# EVSEInterface_ChargerRelay.net
KiCad netlist of a schematic drawn in Altium Designer
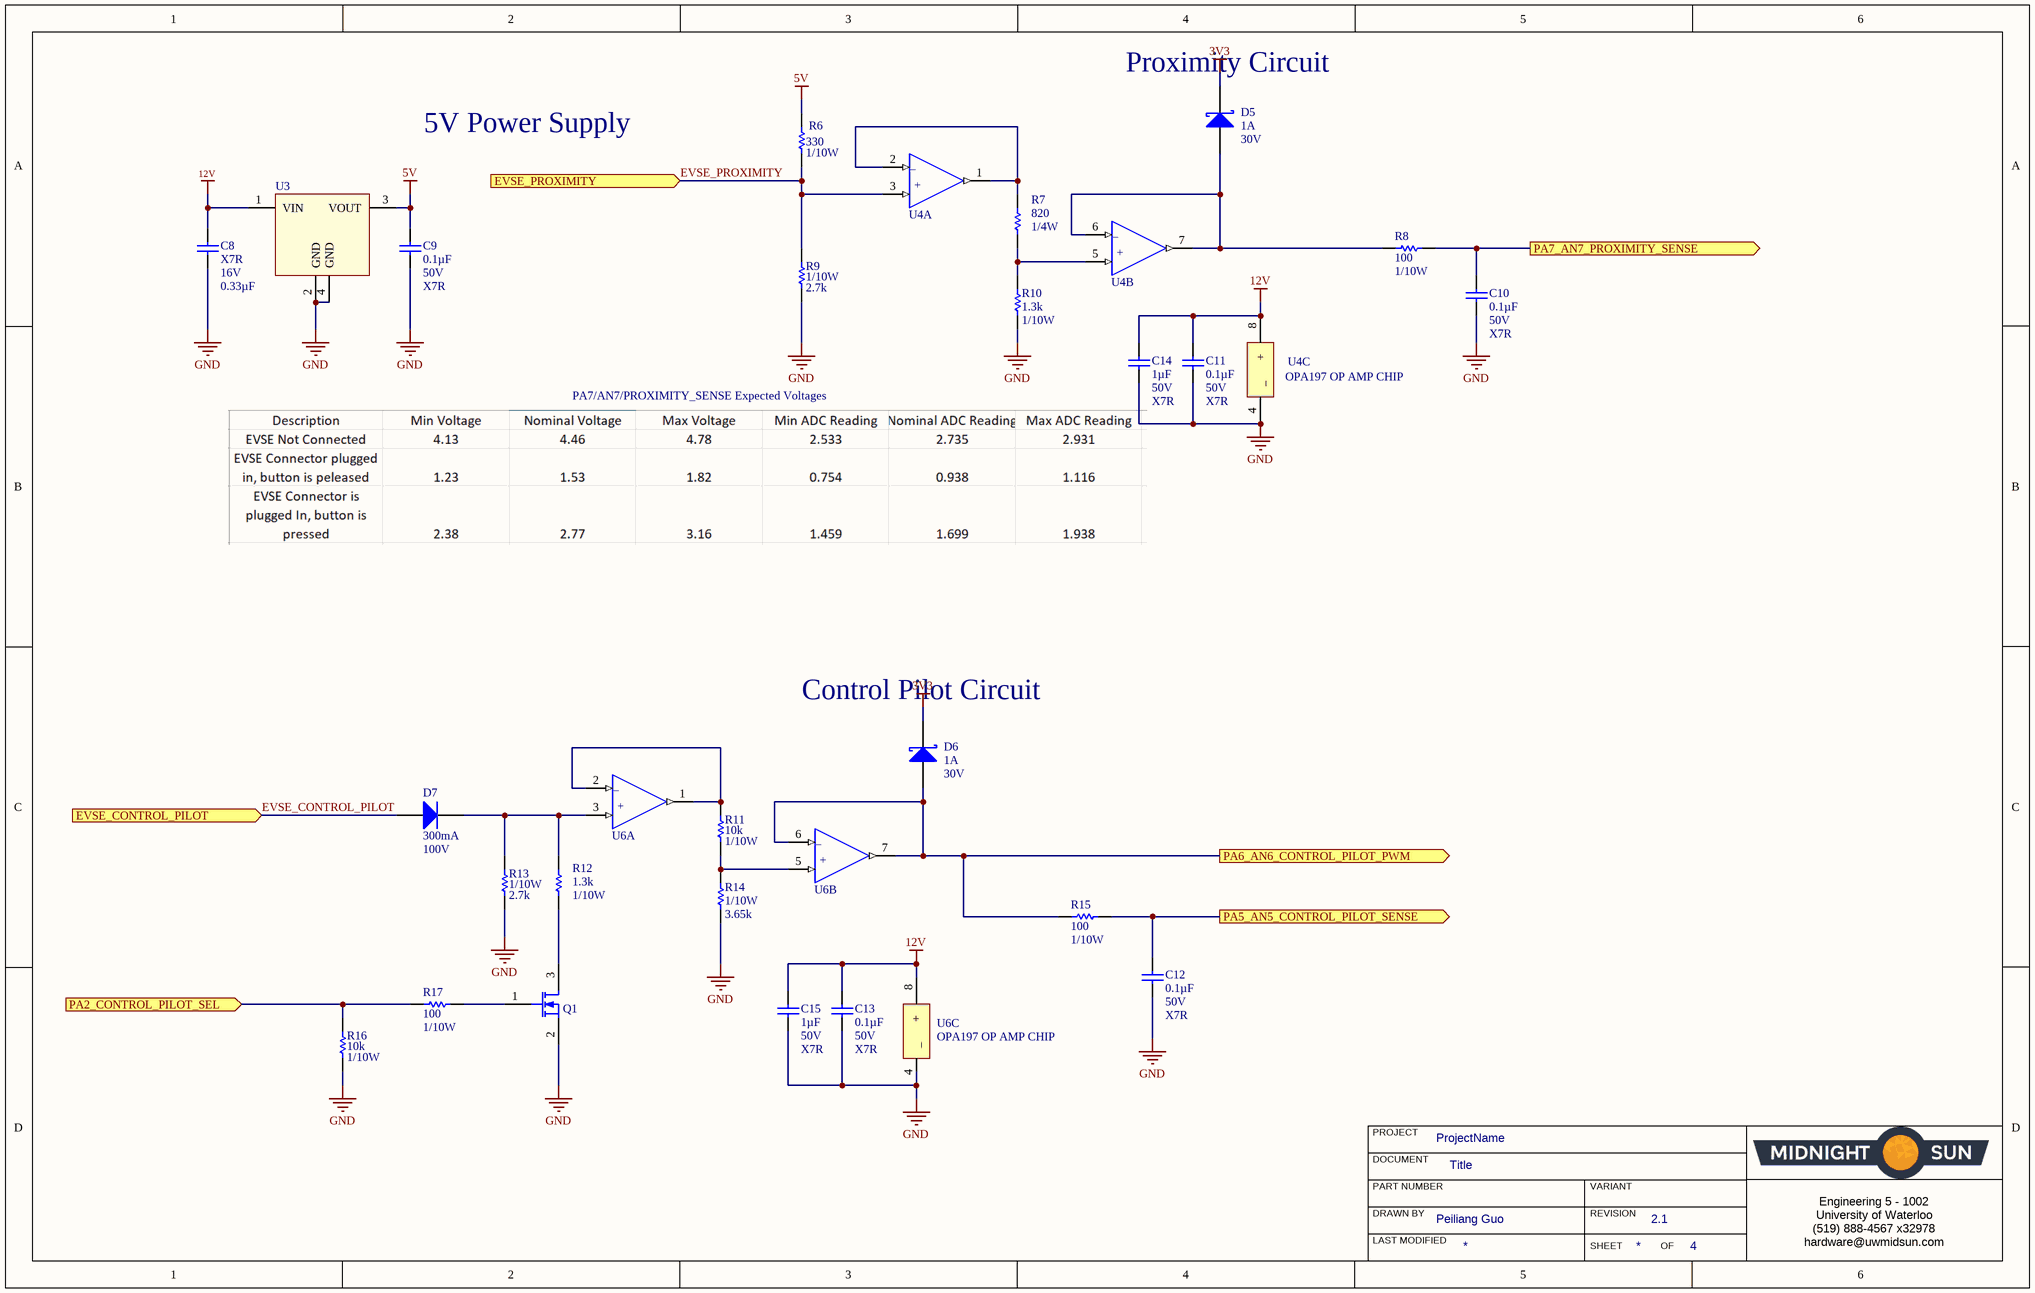
[diagram p0: EVSEInterface&ChargerRelay.SchDoc]

(export (version "E")
  (design (tool "Eeschema 10.0.6"))
  (components
    (comp (ref "C8")
      (value "CAP CER 0.33UF 16V 10% X7R 0603")
      (footprint "CAP, 0603")
      (description "0.33µF ±10% 16V Ceramic Capacitor X7R 0603 (1608 Metric)")
      (fields
        (field (name "MANUFACTURER") "KEMET")
        (field (name "MANUFACTURER PART NUMBER") "C0603C334K4RACTU")
        (field (name "DIELECTRIC") "X7R")
        (field (name "VOLTAGE") "16V")
        (field (name "CAPACITANCE") "0.33µF")
      )
      (libsource (lib "Schematic Diagrams") (part "CAP CER 0.33UF 16V 10% X7R 0603"))
    )
    (comp (ref "C9")
      (value "CAP CER 0.1UF 50V 10% X7R 0603")
      (footprint "CAP, 0603")
      (description "0.10µF ±10% 50V Ceramic Capacitor X7R 0603 (1608 Metric)")
      (fields
        (field (name "TOLERANCE") "±10%")
        (field (name "CAPACITANCE") "0.1µF")
        (field (name "VOLTAGE") "50V")
        (field (name "TEMPERATURE COEFFICIENT") "X7R")
      )
      (libsource (lib "Schematic Diagrams") (part "CAP CER 0.1UF 50V 10% X7R 0603"))
    )
    (comp (ref "C10")
      (value "CAP CER 0.1UF 50V 10% X7R 0603")
      (footprint "CAP, 0603")
      (description "0.10µF ±10% 50V Ceramic Capacitor X7R 0603 (1608 Metric)")
      (fields
        (field (name "TOLERANCE") "±10%")
        (field (name "CAPACITANCE") "0.1µF")
        (field (name "VOLTAGE") "50V")
        (field (name "TEMPERATURE COEFFICIENT") "X7R")
      )
      (libsource (lib "Schematic Diagrams") (part "CAP CER 0.1UF 50V 10% X7R 0603"))
    )
    (comp (ref "C11")
      (value "CAP CER 0.1UF 50V 10% X7R 0603")
      (footprint "CAP, 0603")
      (description "0.10µF ±10% 50V Ceramic Capacitor X7R 0603 (1608 Metric)")
      (fields
        (field (name "TOLERANCE") "±10%")
        (field (name "CAPACITANCE") "0.1µF")
        (field (name "VOLTAGE") "50V")
        (field (name "TEMPERATURE COEFFICIENT") "X7R")
      )
      (libsource (lib "Schematic Diagrams") (part "CAP CER 0.1UF 50V 10% X7R 0603"))
    )
    (comp (ref "C12")
      (value "CAP CER 0.1UF 50V 10% X7R 0603")
      (footprint "CAP, 0603")
      (description "0.10µF ±10% 50V Ceramic Capacitor X7R 0603 (1608 Metric)")
      (fields
        (field (name "TOLERANCE") "±10%")
        (field (name "CAPACITANCE") "0.1µF")
        (field (name "VOLTAGE") "50V")
        (field (name "TEMPERATURE COEFFICIENT") "X7R")
      )
      (libsource (lib "Schematic Diagrams") (part "CAP CER 0.1UF 50V 10% X7R 0603"))
    )
    (comp (ref "C13")
      (value "CAP CER 0.1UF 50V 10% X7R 0603")
      (footprint "CAP, 0603")
      (description "0.10µF ±10% 50V Ceramic Capacitor X7R 0603 (1608 Metric)")
      (fields
        (field (name "TOLERANCE") "±10%")
        (field (name "CAPACITANCE") "0.1µF")
        (field (name "VOLTAGE") "50V")
        (field (name "TEMPERATURE COEFFICIENT") "X7R")
      )
      (libsource (lib "Schematic Diagrams") (part "CAP CER 0.1UF 50V 10% X7R 0603"))
    )
    (comp (ref "C14")
      (value "CAP CER 1UF 50V 10% X7R 0603")
      (footprint "CAP, 0603")
      (description "1µF ±10% 50V Ceramic Capacitor X7R 0603 (1608 Metric)")
      (fields
        (field (name "TOLERANCE") "±10%")
        (field (name "CAPACITANCE") "1µF")
        (field (name "VOLTAGE") "50V")
        (field (name "TEMPERATURE COEFFICIENT") "X7R")
      )
      (libsource (lib "Schematic Diagrams") (part "CAP CER 1UF 50V 10% X7R 0603"))
    )
    (comp (ref "C15")
      (value "CAP CER 1UF 50V 10% X7R 0603")
      (footprint "CAP, 0603")
      (description "1µF ±10% 50V Ceramic Capacitor X7R 0603 (1608 Metric)")
      (fields
        (field (name "TOLERANCE") "±10%")
        (field (name "CAPACITANCE") "1µF")
        (field (name "VOLTAGE") "50V")
        (field (name "TEMPERATURE COEFFICIENT") "X7R")
      )
      (libsource (lib "Schematic Diagrams") (part "CAP CER 1UF 50V 10% X7R 0603"))
    )
    (comp (ref "D5")
      (value "DIODE SCHOTTKY 30V 1A POWERDI123")
      (footprint "DIODE SCHOTTKY 30V 1A POWERDI123")
      (description "Diode Schottky 30V 1A Surface Mount PowerDI™ 123")
      (fields
        (field (name "MANUFACTURER") "Diodes Incorporated")
        (field (name "MANUFACTURER PART NUMBER") "DFLS130L-7")
        (field (name "CURRENT - AVERAGE RECTIFIED (IO)") "1A")
        (field (name "VOLTAGE - DC REVERSE (VR) (MAX)") "30V")
      )
      (libsource (lib "Schematic Diagrams") (part "DIODE SCHOTTKY 30V 1A POWERDI123"))
    )
    (comp (ref "D6")
      (value "DIODE SCHOTTKY 30V 1A POWERDI123")
      (footprint "DIODE SCHOTTKY 30V 1A POWERDI123")
      (description "Diode Schottky 30V 1A Surface Mount PowerDI™ 123")
      (fields
        (field (name "MANUFACTURER") "Diodes Incorporated")
        (field (name "MANUFACTURER PART NUMBER") "DFLS130L-7")
        (field (name "CURRENT - AVERAGE RECTIFIED (IO)") "1A")
        (field (name "VOLTAGE - DC REVERSE (VR) (MAX)") "30V")
      )
      (libsource (lib "Schematic Diagrams") (part "DIODE SCHOTTKY 30V 1A POWERDI123"))
    )
    (comp (ref "D7")
      (value "DIODE GEN PURP 100V 300MA SOD123")
      (footprint "DIODE GEN PURP 100V 300MA SOD123")
      (description "Diode Standard 100V 300mA (DC) Surface Mount SOD-123")
      (fields
        (field (name "MANUFACTURER") "Diodes Zetex")
        (field (name "MANUFACTURER PART NUMBER") "1N4148WQ-7-F")
        (field (name "FORWARD CURRENT") "300mA")
        (field (name "MAX REPETITIVE REVERSE VOLTAGE (VRRM)") "100V")
      )
      (libsource (lib "Schematic Diagrams") (part "DIODE GEN PURP 100V 300MA SOD123"))
    )
    (comp (ref "Q1")
      (value "MOSFET N-CH 30V 6.2A 0.9W SOT-23")
      (footprint "MOSFET N-CH 30V 6.2A 0.9W SOT-23")
      (description "N-Channel 30V 6.2A (Ta) 900mW (Ta) Surface Mount SOT-23")
      (fields (field (name "MANUFACTURER") "Diodes") (field (name "MANUFACTURER PART NUMBER") "DMN3023L-7"))
      (libsource (lib "Schematic Diagrams") (part "MOSFET N-CH 30V 6.2A 0.9W SOT-23"))
    )
    (comp (ref "R6")
      (value "RES 330 OHM 1% 1/10W 0603")
      (footprint "RES, 0603")
      (fields
        (field (name "MANUFACTURER") "TE Connectivity")
        (field (name "MANUFACTURER PART NUMBER") "1-2176339-9")
        (field (name "RESISTANCE") "330")
        (field (name "POWER") "1/10W")
      )
      (libsource (lib "Schematic Diagrams") (part "RES 330 OHM 1% 1/10W 0603"))
    )
    (comp (ref "R7")
      (value "RES 820 OHM 5% 1/4W 0603")
      (footprint "RES, 0603")
      (description "RES SMD 820 OHM 5% 1/4W 0603")
      (fields
        (field (name "TOLERANCE") "±5%")
        (field (name "RESISTANCE") "820")
        (field (name "POWER") "1/4W")
      )
      (libsource (lib "Schematic Diagrams") (part "RES 820 OHM 5% 1/4W 0603"))
    )
    (comp (ref "R8")
      (value "RES 100 OHM 1% 1/10W 0603")
      (footprint "RES, 0603")
      (description "100 Ohm ±1% 0.1W, 1/10W Chip Resistor 0603 (1608 Metric) Moisture Resistant Thick Film")
      (fields
        (field (name "TOLERANCE") "±1%")
        (field (name "RESISTANCE") "100")
        (field (name "POWER") "1/10W")
      )
      (libsource (lib "Schematic Diagrams") (part "RES 100 OHM 1% 1/10W 0603"))
    )
    (comp (ref "R9")
      (value "RES 2.7K OHM 1% 1/10W 0603")
      (footprint "RES, 0603")
      (fields
        (field (name "MANUFACTURER") "TE Connectivity")
        (field (name "MANUFACTURER PART NUMBER") "3-2176339-0")
        (field (name "POWER") "1/10W")
        (field (name "RESISTANCE") "2.7k")
      )
      (libsource (lib "Schematic Diagrams") (part "RES 2.7K OHM 1% 1/10W 0603"))
    )
    (comp (ref "R10")
      (value "RES 1.3K OHM 1% 1/10W 0603")
      (footprint "RES, 0603")
      (description "1.3 kOhms ±1% 0.1W, 1/10W Chip Resistor 0603 (1608 Metric) Moisture Resistant Thick Film")
      (fields
        (field (name "MANUFACTURER") "Yageo")
        (field (name "MANUFACTURER PART NUMBER") "RC0603FR-071K3L")
        (field (name "RESISTANCE") "1.3k")
        (field (name "POWER RATING") "1/10W")
      )
      (libsource (lib "Schematic Diagrams") (part "RES 1.3K OHM 1% 1/10W 0603"))
    )
    (comp (ref "R11")
      (value "RES 10K OHM 1% 1/10W 0603")
      (footprint "RES, 0603")
      (description "RES SMD 10K OHM 1% 1/10W 0603")
      (fields
        (field (name "TOLERANCE") "±1%")
        (field (name "RESISTANCE") "10k")
        (field (name "POWER") "1/10W")
      )
      (libsource (lib "Schematic Diagrams") (part "RES 10K OHM 1% 1/10W 0603"))
    )
    (comp (ref "R12")
      (value "RES 1.3K OHM 1% 1/10W 0603")
      (footprint "RES, 0603")
      (description "1.3 kOhms ±1% 0.1W, 1/10W Chip Resistor 0603 (1608 Metric) Moisture Resistant Thick Film")
      (fields
        (field (name "MANUFACTURER") "Yageo")
        (field (name "MANUFACTURER PART NUMBER") "RC0603FR-071K3L")
        (field (name "RESISTANCE") "1.3k")
        (field (name "POWER RATING") "1/10W")
      )
      (libsource (lib "Schematic Diagrams") (part "RES 1.3K OHM 1% 1/10W 0603"))
    )
    (comp (ref "R13")
      (value "RES 2.7K OHM 1% 1/10W 0603")
      (footprint "RES, 0603")
      (fields
        (field (name "MANUFACTURER") "TE Connectivity")
        (field (name "MANUFACTURER PART NUMBER") "3-2176339-0")
        (field (name "POWER") "1/10W")
        (field (name "RESISTANCE") "2.7k")
      )
      (libsource (lib "Schematic Diagrams") (part "RES 2.7K OHM 1% 1/10W 0603"))
    )
    (comp (ref "R14")
      (value "RES 3.65K OHM 0.1% 1/10W 0603")
      (footprint "RES, 0603")
      (description "3.65 kOhms ±0.1% 0.1W, 1/10W Chip Resistor 0603 (1608 Metric) Automotive AEC-Q200 Thin Film")
      (fields
        (field (name "MANUFACTURER") "Panasonic")
        (field (name "MANUFACTURER PART NUMBER") "ERA3AEB3651V")
        (field (name "POWER RATING") "1/10W")
        (field (name "RESISTANCE") "3.65k")
      )
      (libsource (lib "Schematic Diagrams") (part "RES 3.65K OHM 0.1% 1/10W 0603"))
    )
    (comp (ref "R15")
      (value "RES 100 OHM 1% 1/10W 0603")
      (footprint "RES, 0603")
      (description "100 Ohm ±1% 0.1W, 1/10W Chip Resistor 0603 (1608 Metric) Moisture Resistant Thick Film")
      (fields
        (field (name "TOLERANCE") "±1%")
        (field (name "RESISTANCE") "100")
        (field (name "POWER") "1/10W")
      )
      (libsource (lib "Schematic Diagrams") (part "RES 100 OHM 1% 1/10W 0603"))
    )
    (comp (ref "R16")
      (value "RES 10K OHM 1% 1/10W 0603")
      (footprint "RES, 0603")
      (description "RES SMD 10K OHM 1% 1/10W 0603")
      (fields
        (field (name "TOLERANCE") "±1%")
        (field (name "RESISTANCE") "10k")
        (field (name "POWER") "1/10W")
      )
      (libsource (lib "Schematic Diagrams") (part "RES 10K OHM 1% 1/10W 0603"))
    )
    (comp (ref "R17")
      (value "RES 100 OHM 1% 1/10W 0603")
      (footprint "RES, 0603")
      (description "100 Ohm ±1% 0.1W, 1/10W Chip Resistor 0603 (1608 Metric) Moisture Resistant Thick Film")
      (fields
        (field (name "TOLERANCE") "±1%")
        (field (name "RESISTANCE") "100")
        (field (name "POWER") "1/10W")
      )
      (libsource (lib "Schematic Diagrams") (part "RES 100 OHM 1% 1/10W 0603"))
    )
    (comp (ref "U3")
      (value "IC REG LDO 5V 0.5A SOT223")
      (footprint "SOT223_N")
      (description "Linear Voltage Regulator IC Positive Fixed Output 5V 500mA SOT-223-4")
      (libsource (lib "Schematic Diagrams") (part "IC REG LDO 5V 0.5A SOT223"))
    )
    (comp (ref "U4")
      (value "IC OP AMP DUAL GP RR 10MHZ 8-VSSOP")
      (footprint "IC OP AMP DUAL 8-VSSOP")
      (description "General Purpose Amplifier 2 Circuit Rail-to-Rail 8-VSSOP")
      (fields
        (field (name "MANUFACTURER") "Texas Instruments")
        (field (name "MANUFACTURER PART NUMBER") "OPA2197IDGKR")
      )
      (libsource (lib "") (part "IC OP AMP DUAL GP RR 10MHZ 8-VSSOP_1"))
    )
    (comp (ref "U6")
      (value "IC OP AMP DUAL GP RR 10MHZ 8-VSSOP")
      (footprint "IC OP AMP DUAL 8-VSSOP")
      (description "General Purpose Amplifier 2 Circuit Rail-to-Rail 8-VSSOP")
      (fields
        (field (name "MANUFACTURER") "Texas Instruments")
        (field (name "MANUFACTURER PART NUMBER") "OPA2197IDGKR")
      )
      (libsource (lib "Schematic Diagrams") (part "IC OP AMP DUAL GP RR 10MHZ 8-VSSOP"))
    )
  )
  (nets
    (net (code "1") (name "/EVSE_CONTROL_PILOT") (class "Default")
      (node (ref "D7") (pin "1") (pinfunction "A_1") (pintype "passive"))
    )
    (net (code "2") (name "/EVSE_PROXIMITY") (class "Default")
      (node (ref "R6") (pin "2") (pinfunction "2_2") (pintype "passive"))
      (node (ref "R9") (pin "1") (pinfunction "1_1") (pintype "passive"))
      (node (ref "U4") (pin "3") (pinfunction "+IN_A_3") (pintype "input"))
    )
    (net (code "3") (name "/PA2_CONTROL_PILOT_SEL") (class "Default")
      (node (ref "R16") (pin "1") (pinfunction "1_1") (pintype "passive"))
      (node (ref "R17") (pin "1") (pinfunction "1_1") (pintype "passive"))
    )
    (net (code "4") (name "/PA5_AN5_CONTROL_PILOT_SENSE") (class "Default")
      (node (ref "C12") (pin "1") (pinfunction "1_1") (pintype "passive"))
      (node (ref "R15") (pin "2") (pinfunction "2_2") (pintype "passive"))
    )
    (net (code "5") (name "/PA6_AN6_CONTROL_PILOT_PWM") (class "Default")
      (node (ref "D6") (pin "1") (pinfunction "A_1") (pintype "passive"))
      (node (ref "R15") (pin "1") (pinfunction "1_1") (pintype "passive"))
      (node (ref "U6") (pin "6") (pinfunction "-IN_B_6") (pintype "input"))
      (node (ref "U6") (pin "7") (pinfunction "OUT_B_7") (pintype "output"))
    )
    (net (code "6") (name "/PA7_AN7_PROXIMITY_SENSE") (class "Default")
      (node (ref "C10") (pin "1") (pinfunction "1_1") (pintype "passive"))
      (node (ref "R8") (pin "2") (pinfunction "2_2") (pintype "passive"))
    )
    (net (code "7") (name "3V3") (class "Default")
      (node (ref "D5") (pin "2") (pinfunction "K_2") (pintype "passive"))
      (node (ref "D6") (pin "2") (pinfunction "K_2") (pintype "passive"))
    )
    (net (code "8") (name "5V") (class "Default")
      (node (ref "C9") (pin "1") (pinfunction "1_1") (pintype "passive"))
      (node (ref "R6") (pin "1") (pinfunction "1_1") (pintype "passive"))
      (node (ref "U3") (pin "3") (pinfunction "VOUT_3") (pintype "power_in"))
    )
    (net (code "9") (name "12V") (class "Default")
      (node (ref "C11") (pin "1") (pinfunction "1_1") (pintype "passive"))
      (node (ref "C13") (pin "1") (pinfunction "1_1") (pintype "passive"))
      (node (ref "C14") (pin "1") (pinfunction "1_1") (pintype "passive"))
      (node (ref "C15") (pin "1") (pinfunction "1_1") (pintype "passive"))
      (node (ref "C8") (pin "1") (pinfunction "1_1") (pintype "passive"))
      (node (ref "U3") (pin "1") (pinfunction "VIN_1") (pintype "power_in"))
      (node (ref "U4") (pin "8") (pinfunction "+_8") (pintype "power_in"))
      (node (ref "U6") (pin "8") (pinfunction "+_8") (pintype "power_in"))
    )
    (net (code "10") (name "GND") (class "Default")
      (node (ref "C10") (pin "2") (pinfunction "2_2") (pintype "passive"))
      (node (ref "C11") (pin "2") (pinfunction "2_2") (pintype "passive"))
      (node (ref "C12") (pin "2") (pinfunction "2_2") (pintype "passive"))
      (node (ref "C13") (pin "2") (pinfunction "2_2") (pintype "passive"))
      (node (ref "C14") (pin "2") (pinfunction "2_2") (pintype "passive"))
      (node (ref "C15") (pin "2") (pinfunction "2_2") (pintype "passive"))
      (node (ref "C8") (pin "2") (pinfunction "2_2") (pintype "passive"))
      (node (ref "C9") (pin "2") (pinfunction "2_2") (pintype "passive"))
      (node (ref "Q1") (pin "2") (pinfunction "S_2") (pintype "passive"))
      (node (ref "R10") (pin "2") (pinfunction "2_2") (pintype "passive"))
      (node (ref "R13") (pin "2") (pinfunction "2_2") (pintype "passive"))
      (node (ref "R14") (pin "2") (pinfunction "2_2") (pintype "passive"))
      (node (ref "R16") (pin "2") (pinfunction "2_2") (pintype "passive"))
      (node (ref "R9") (pin "2") (pinfunction "2_2") (pintype "passive"))
      (node (ref "U3") (pin "2") (pinfunction "GND_2") (pintype "power_in"))
      (node (ref "U3") (pin "4") (pinfunction "GND_4") (pintype "power_in"))
      (node (ref "U4") (pin "4") (pinfunction "__4") (pintype "power_in"))
      (node (ref "U6") (pin "4") (pinfunction "__4") (pintype "power_in"))
    )
    (net (code "11") (name "Net-(D5-A)") (class "Default")
      (node (ref "D5") (pin "1") (pinfunction "A_1") (pintype "passive"))
      (node (ref "R8") (pin "1") (pinfunction "1_1") (pintype "passive"))
      (node (ref "U4") (pin "6") (pinfunction "-IN_B_6") (pintype "input"))
      (node (ref "U4") (pin "7") (pinfunction "OUT_B_7") (pintype "output"))
    )
    (net (code "12") (name "Net-(D7-K)") (class "Default")
      (node (ref "D7") (pin "2") (pinfunction "K_2") (pintype "passive"))
      (node (ref "R12") (pin "1") (pinfunction "1_1") (pintype "passive"))
      (node (ref "R13") (pin "1") (pinfunction "1_1") (pintype "passive"))
      (node (ref "U6") (pin "3") (pinfunction "+IN_A_3") (pintype "input"))
    )
    (net (code "13") (name "Net-(Q1-D)") (class "Default")
      (node (ref "Q1") (pin "3") (pinfunction "D_3") (pintype "passive"))
      (node (ref "R12") (pin "2") (pinfunction "2_2") (pintype "passive"))
    )
    (net (code "14") (name "Net-(Q1-G)") (class "Default")
      (node (ref "Q1") (pin "1") (pinfunction "G_1") (pintype "passive"))
      (node (ref "R17") (pin "2") (pinfunction "2_2") (pintype "passive"))
    )
    (net (code "15") (name "Net-(U4A--IN_A)") (class "Default")
      (node (ref "R7") (pin "1") (pinfunction "1_1") (pintype "passive"))
      (node (ref "U4") (pin "1") (pinfunction "OUT_A_1") (pintype "output"))
      (node (ref "U4") (pin "2") (pinfunction "-IN_A_2") (pintype "input"))
    )
    (net (code "16") (name "Net-(U4B-+IN_B)") (class "Default")
      (node (ref "R10") (pin "1") (pinfunction "1_1") (pintype "passive"))
      (node (ref "R7") (pin "2") (pinfunction "2_2") (pintype "passive"))
      (node (ref "U4") (pin "5") (pinfunction "+IN_B_5") (pintype "input"))
    )
    (net (code "17") (name "Net-(U6A--IN_A)") (class "Default")
      (node (ref "R11") (pin "1") (pinfunction "1_1") (pintype "passive"))
      (node (ref "U6") (pin "1") (pinfunction "OUT_A_1") (pintype "output"))
      (node (ref "U6") (pin "2") (pinfunction "-IN_A_2") (pintype "input"))
    )
    (net (code "18") (name "Net-(U6B-+IN_B)") (class "Default")
      (node (ref "R11") (pin "2") (pinfunction "2_2") (pintype "passive"))
      (node (ref "R14") (pin "1") (pinfunction "1_1") (pintype "passive"))
      (node (ref "U6") (pin "5") (pinfunction "+IN_B_5") (pintype "input"))
    )
  )
)
